# tach_adapter.net
KiCad netlist of a schematic drawn in EAGLE
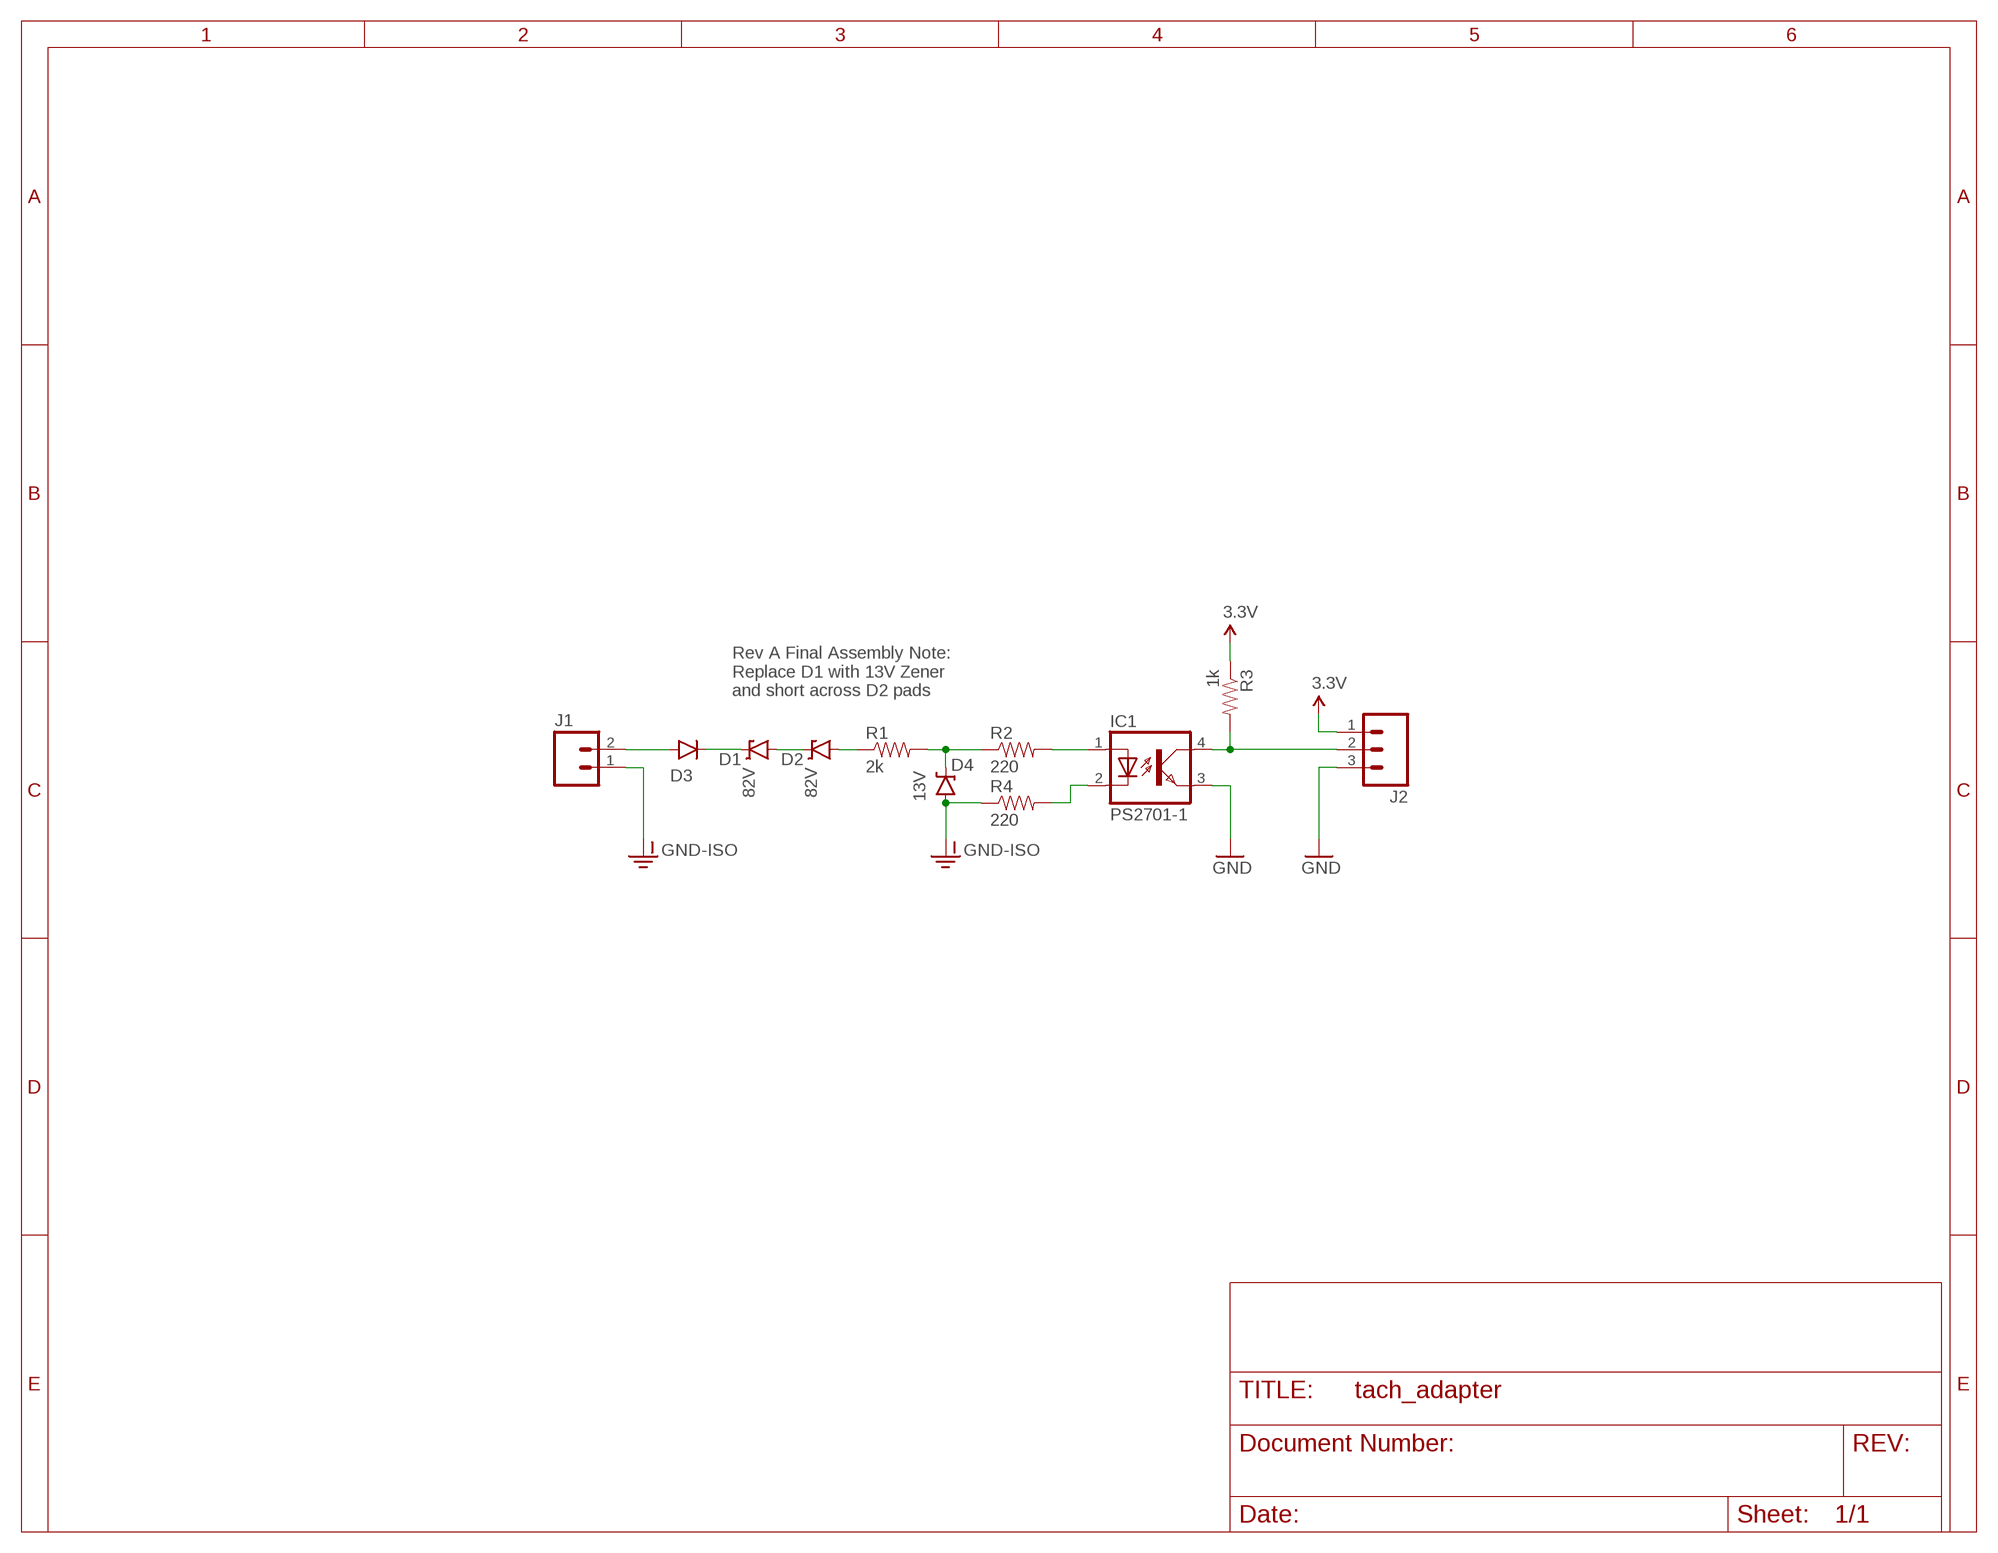
[diagram p0: schematic, sheet 1]

(export (version "E")
  (design (tool "Eeschema 10.0.6"))
  (components
    (comp (ref "D1")
      (value "82V")
      (footprint "eagle-import:SMB-DIODE")
      (libsource (lib "eagle-import") (part "DIODE-ZENERSMB"))
    )
    (comp (ref "D2")
      (value "82V")
      (footprint "eagle-import:SMB-DIODE")
      (libsource (lib "eagle-import") (part "DIODE-ZENERSMB"))
    )
    (comp (ref "D3")
      (value "DIODESMA")
      (footprint "eagle-import:SMA-DIODE")
      (libsource (lib "eagle-import") (part "DIODESMA"))
    )
    (comp (ref "D4")
      (value "13V")
      (footprint "eagle-import:SMB-DIODE")
      (libsource (lib "eagle-import") (part "DIODE-ZENERSMB"))
    )
    (comp (ref "IC1")
      (value "PS2701-1")
      (footprint "eagle-import:4-SMD")
      (libsource (lib "eagle-import") (part "PS2701-1"))
    )
    (comp (ref "J1")
      (value "M02PTH3")
      (footprint "eagle-import:1X02_LONGPADS")
      (libsource (lib "eagle-import") (part "M02PTH3"))
    )
    (comp (ref "J2")
      (value "M03LONGPADS")
      (footprint "eagle-import:1X03_LONGPADS")
      (libsource (lib "eagle-import") (part "M03LONGPADS"))
    )
    (comp (ref "R1")
      (value "2k")
      (footprint "eagle-import:1206")
      (libsource (lib "eagle-import") (part "RESISTOR1206"))
    )
    (comp (ref "R2")
      (value "220")
      (footprint "eagle-import:1206")
      (libsource (lib "eagle-import") (part "RESISTOR1206"))
    )
    (comp (ref "R3")
      (value "1k")
      (footprint "eagle-import:1206")
      (libsource (lib "eagle-import") (part "RESISTOR1206"))
    )
    (comp (ref "R4")
      (value "220")
      (footprint "eagle-import:1206")
      (libsource (lib "eagle-import") (part "RESISTOR1206"))
    )
  )
  (nets
    (net (code "1") (name "3.3V") (class "Default")
      (node (ref "J2") (pin "1") (pinfunction "1_1") (pintype "passive"))
      (node (ref "R3") (pin "1") (pinfunction "1_1") (pintype "passive"))
    )
    (net (code "2") (name "GND") (class "Default")
      (node (ref "IC1") (pin "3") (pinfunction "EMIT_3") (pintype "passive"))
      (node (ref "J2") (pin "3") (pinfunction "3_3") (pintype "passive"))
    )
    (net (code "3") (name "GND-ISO") (class "Default")
      (node (ref "D4") (pin "A") (pinfunction "A_A") (pintype "passive"))
      (node (ref "J1") (pin "1") (pinfunction "1_1") (pintype "passive"))
      (node (ref "R4") (pin "1") (pinfunction "1_1") (pintype "passive"))
    )
    (net (code "4") (name "Net-(D1-PadA)") (class "Default")
      (node (ref "D1") (pin "A") (pinfunction "A_A") (pintype "passive"))
      (node (ref "D2") (pin "C") (pinfunction "C_C") (pintype "passive"))
    )
    (net (code "5") (name "Net-(D1-PadC)") (class "Default")
      (node (ref "D1") (pin "C") (pinfunction "C_C") (pintype "passive"))
      (node (ref "D3") (pin "C") (pinfunction "C_C") (pintype "passive"))
    )
    (net (code "6") (name "Net-(D2-PadA)") (class "Default")
      (node (ref "D2") (pin "A") (pinfunction "A_A") (pintype "passive"))
      (node (ref "R1") (pin "1") (pinfunction "1_1") (pintype "passive"))
    )
    (net (code "7") (name "Net-(D3-PadA)") (class "Default")
      (node (ref "D3") (pin "A") (pinfunction "A_A") (pintype "passive"))
      (node (ref "J1") (pin "2") (pinfunction "2_2") (pintype "passive"))
    )
    (net (code "8") (name "Net-(D4-PadC)") (class "Default")
      (node (ref "D4") (pin "C") (pinfunction "C_C") (pintype "passive"))
      (node (ref "R1") (pin "2") (pinfunction "2_2") (pintype "passive"))
      (node (ref "R2") (pin "1") (pinfunction "1_1") (pintype "passive"))
    )
    (net (code "9") (name "Net-(IC1-A)") (class "Default")
      (node (ref "IC1") (pin "1") (pinfunction "A_1") (pintype "passive"))
      (node (ref "R2") (pin "2") (pinfunction "2_2") (pintype "passive"))
    )
    (net (code "10") (name "Net-(IC1-C)") (class "Default")
      (node (ref "IC1") (pin "2") (pinfunction "C_2") (pintype "passive"))
      (node (ref "R4") (pin "2") (pinfunction "2_2") (pintype "passive"))
    )
    (net (code "11") (name "Net-(IC1-COL)") (class "Default")
      (node (ref "IC1") (pin "4") (pinfunction "COL_4") (pintype "passive"))
      (node (ref "J2") (pin "2") (pinfunction "2_2") (pintype "passive"))
      (node (ref "R3") (pin "2") (pinfunction "2_2") (pintype "passive"))
    )
  )
)
